# myDuinoMini_v1_0.net
KiCad netlist of a schematic drawn in EAGLE
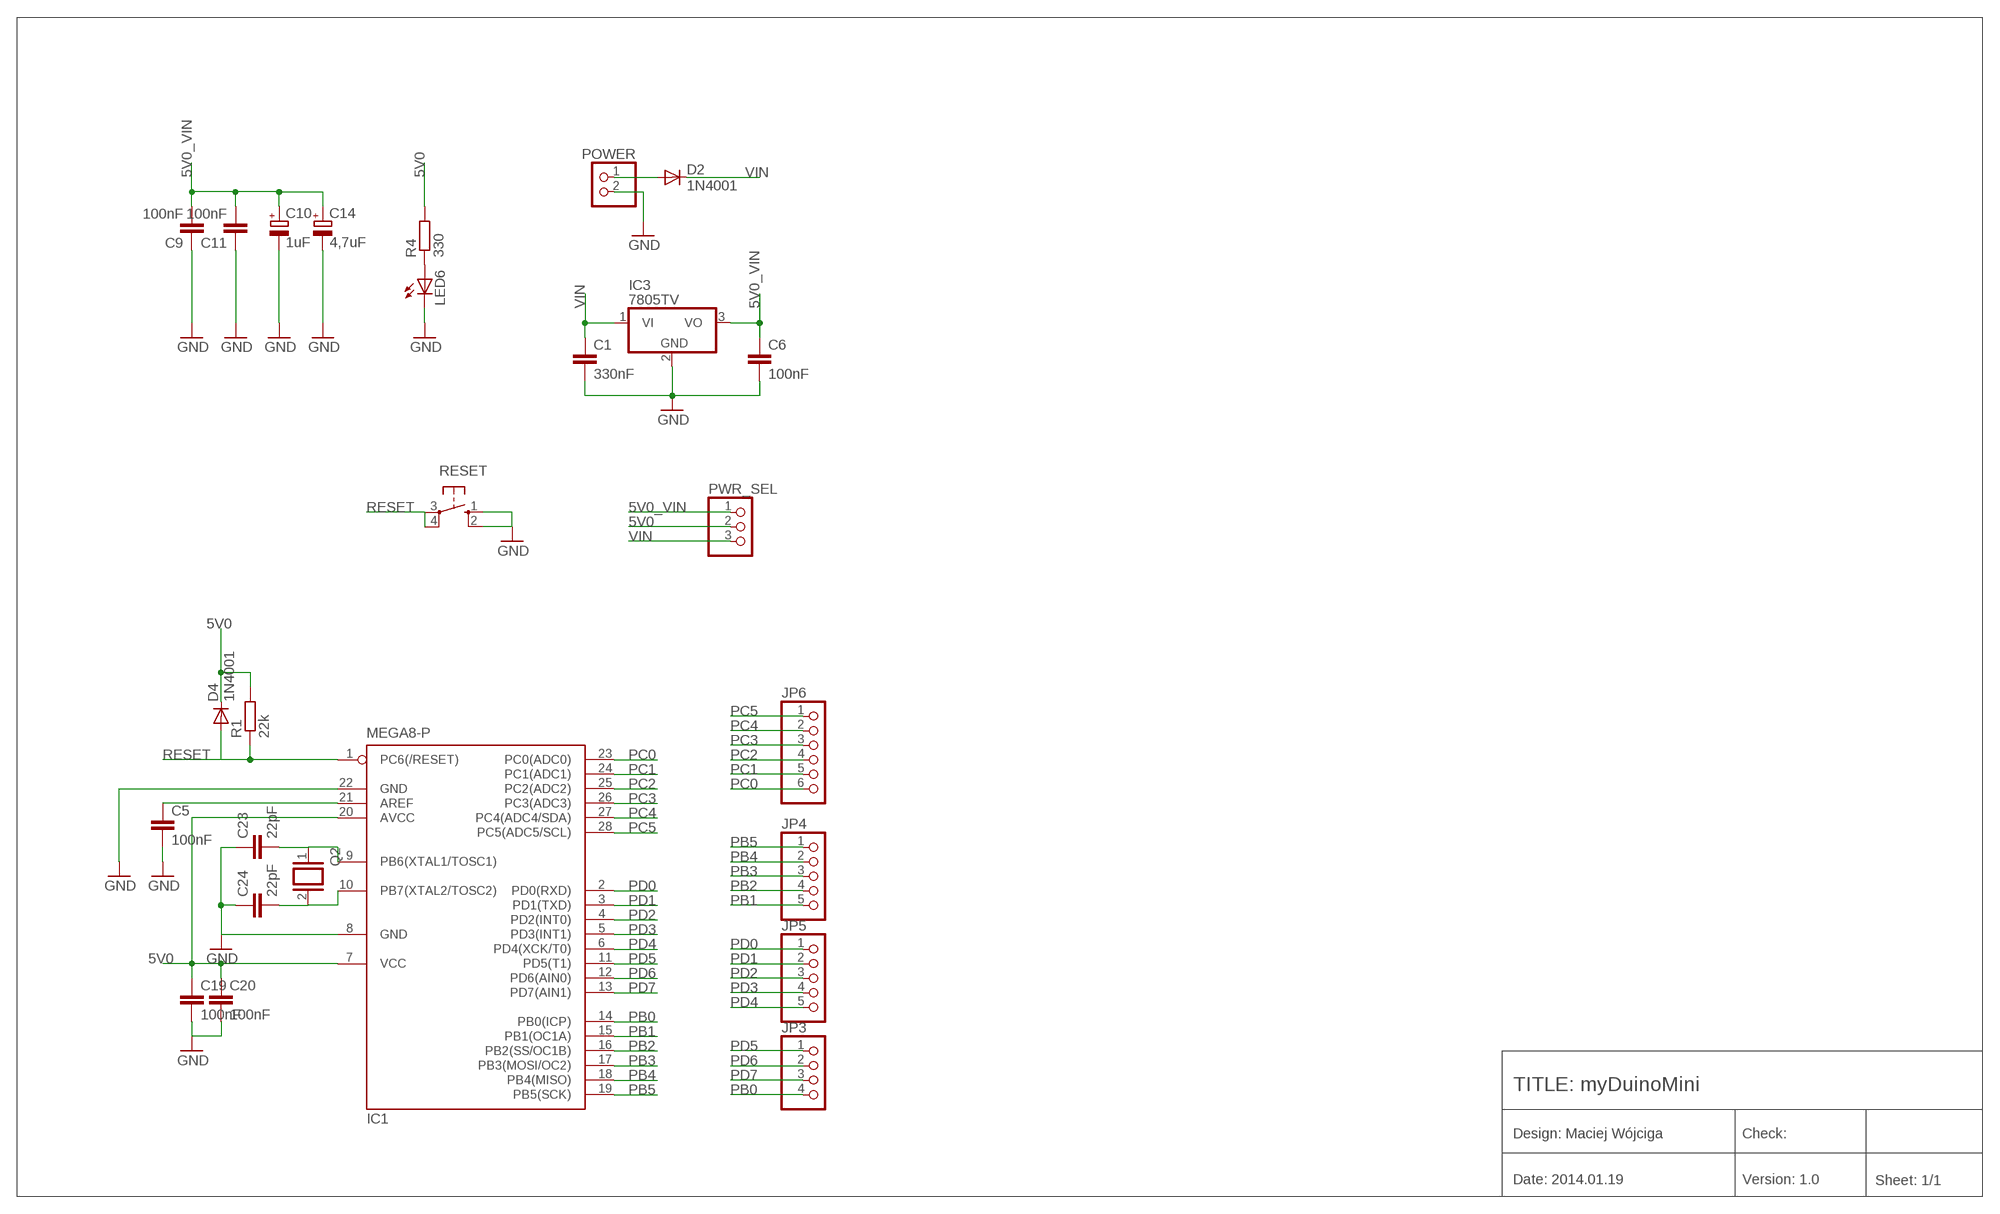
[diagram p0: schematic, sheet 1]

(export (version "E")
  (design (tool "Eeschema 10.0.6"))
  (components
    (comp (ref "C1")
      (value "330nF")
      (footprint "eagle-import:C025-025X050")
      (libsource (lib "eagle-import") (part "C-EU025-025X050"))
    )
    (comp (ref "C5")
      (value "100nF")
      (footprint "eagle-import:C025-025X050")
      (libsource (lib "eagle-import") (part "C-EU025-025X050"))
    )
    (comp (ref "C6")
      (value "100nF")
      (footprint "eagle-import:C025-025X050")
      (libsource (lib "eagle-import") (part "C-EU025-025X050"))
    )
    (comp (ref "C9")
      (value "100nF")
      (footprint "eagle-import:C025-025X050")
      (libsource (lib "eagle-import") (part "C-EU025-025X050"))
    )
    (comp (ref "C10")
      (value "1uF")
      (footprint "eagle-import:E2,5-5")
      (libsource (lib "eagle-import") (part "CPOL-EUE2.5-5"))
    )
    (comp (ref "C11")
      (value "100nF")
      (footprint "eagle-import:C025-025X050")
      (libsource (lib "eagle-import") (part "C-EU025-025X050"))
    )
    (comp (ref "C14")
      (value "4,7uF")
      (footprint "eagle-import:E2,5-5")
      (libsource (lib "eagle-import") (part "CPOL-EUE2.5-5"))
    )
    (comp (ref "C19")
      (value "100nF")
      (footprint "eagle-import:C025-025X050")
      (libsource (lib "eagle-import") (part "C-EU025-025X050"))
    )
    (comp (ref "C20")
      (value "100nF")
      (footprint "eagle-import:C025-025X050")
      (libsource (lib "eagle-import") (part "C-EU025-025X050"))
    )
    (comp (ref "C23")
      (value "22pF")
      (footprint "eagle-import:C025-025X050")
      (libsource (lib "eagle-import") (part "C-EU025-025X050"))
    )
    (comp (ref "C24")
      (value "22pF")
      (footprint "eagle-import:C025-025X050")
      (libsource (lib "eagle-import") (part "C-EU025-025X050"))
    )
    (comp (ref "D2")
      (value "1N4001")
      (footprint "eagle-import:DO41-10")
      (libsource (lib "eagle-import") (part "1N4004"))
    )
    (comp (ref "D4")
      (value "1N4001")
      (footprint "eagle-import:DO41-10")
      (libsource (lib "eagle-import") (part "1N4004"))
    )
    (comp (ref "IC1")
      (value "MEGA8-P")
      (footprint "eagle-import:DIL28-3")
      (libsource (lib "eagle-import") (part "MEGA8-P"))
    )
    (comp (ref "IC3")
      (value "7805TV")
      (footprint "eagle-import:TO220V")
      (libsource (lib "eagle-import") (part "78TV05"))
    )
    (comp (ref "JP3")
      (value "PINHD-1X4")
      (footprint "eagle-import:1X04")
      (libsource (lib "eagle-import") (part "PINHD-1X4"))
    )
    (comp (ref "JP4")
      (value "PINHD-1X5")
      (footprint "eagle-import:1X05")
      (libsource (lib "eagle-import") (part "PINHD-1X5"))
    )
    (comp (ref "JP5")
      (value "PINHD-1X5")
      (footprint "eagle-import:1X05")
      (libsource (lib "eagle-import") (part "PINHD-1X5"))
    )
    (comp (ref "JP6")
      (value "PINHD-1X6")
      (footprint "eagle-import:1X06")
      (libsource (lib "eagle-import") (part "PINHD-1X6"))
    )
    (comp (ref "LED6")
      (value "LED3MM")
      (footprint "eagle-import:LED3MM")
      (libsource (lib "eagle-import") (part "LED3MM"))
    )
    (comp (ref "POWER")
      (value "PINHD-1X2")
      (footprint "eagle-import:1X02")
      (libsource (lib "eagle-import") (part "PINHD-1X2"))
    )
    (comp (ref "PWR_SEL")
      (value "PINHD-1X3")
      (footprint "eagle-import:1X03")
      (libsource (lib "eagle-import") (part "PINHD-1X3"))
    )
    (comp (ref "Q2")
      (value "XTAL/S")
      (footprint "eagle-import:QS")
      (libsource (lib "eagle-import") (part "XTAL/S"))
    )
    (comp (ref "R1")
      (value "22k")
      (footprint "eagle-import:0207_10")
      (libsource (lib "eagle-import") (part "R-EU_0207/10"))
    )
    (comp (ref "R4")
      (value "330")
      (footprint "eagle-import:0207_10")
      (libsource (lib "eagle-import") (part "R-EU_0207/10"))
    )
    (comp (ref "RESET")
      (value "10-XX")
      (footprint "eagle-import:B3F-10XX")
      (fields (field (name "MPN") "B3F-1000"))
      (libsource (lib "eagle-import") (part "10-XX"))
    )
  )
  (nets
    (net (code "1") (name "/5V0") (class "Default")
      (node (ref "C19") (pin "1") (pinfunction "1_1") (pintype "passive"))
      (node (ref "C20") (pin "1") (pinfunction "1_1") (pintype "passive"))
      (node (ref "D4") (pin "C") (pinfunction "C_C") (pintype "passive"))
      (node (ref "IC1") (pin "20") (pinfunction "AVCC_20") (pintype "power_in"))
      (node (ref "IC1") (pin "7") (pinfunction "VCC_7") (pintype "power_in"))
      (node (ref "PWR_SEL") (pin "2") (pinfunction "2_2") (pintype "passive"))
      (node (ref "R1") (pin "2") (pinfunction "2_2") (pintype "passive"))
      (node (ref "R4") (pin "2") (pinfunction "2_2") (pintype "passive"))
    )
    (net (code "2") (name "/5V0_VIN") (class "Default")
      (node (ref "C10") (pin "+") (pinfunction "+_+") (pintype "passive"))
      (node (ref "C11") (pin "2") (pinfunction "2_2") (pintype "passive"))
      (node (ref "C14") (pin "+") (pinfunction "+_+") (pintype "passive"))
      (node (ref "C6") (pin "1") (pinfunction "1_1") (pintype "passive"))
      (node (ref "C9") (pin "2") (pinfunction "2_2") (pintype "passive"))
      (node (ref "IC3") (pin "3") (pinfunction "VO_3") (pintype "passive"))
      (node (ref "PWR_SEL") (pin "1") (pinfunction "1_1") (pintype "passive"))
    )
    (net (code "3") (name "/PB0") (class "Default")
      (node (ref "IC1") (pin "14") (pinfunction "PB0(ICP)_14") (pintype "bidirectional"))
      (node (ref "JP3") (pin "4") (pinfunction "4_4") (pintype "passive"))
    )
    (net (code "4") (name "/PB1") (class "Default")
      (node (ref "IC1") (pin "15") (pinfunction "PB1(OC1A)_15") (pintype "bidirectional"))
      (node (ref "JP4") (pin "5") (pinfunction "5_5") (pintype "passive"))
    )
    (net (code "5") (name "/PB2") (class "Default")
      (node (ref "IC1") (pin "16") (pinfunction "PB2(SS/OC1B)_16") (pintype "bidirectional"))
      (node (ref "JP4") (pin "4") (pinfunction "4_4") (pintype "passive"))
    )
    (net (code "6") (name "/PB3") (class "Default")
      (node (ref "IC1") (pin "17") (pinfunction "PB3(MOSI/OC2)_17") (pintype "bidirectional"))
      (node (ref "JP4") (pin "3") (pinfunction "3_3") (pintype "passive"))
    )
    (net (code "7") (name "/PB4") (class "Default")
      (node (ref "IC1") (pin "18") (pinfunction "PB4(MISO)_18") (pintype "bidirectional"))
      (node (ref "JP4") (pin "2") (pinfunction "2_2") (pintype "passive"))
    )
    (net (code "8") (name "/PB5") (class "Default")
      (node (ref "IC1") (pin "19") (pinfunction "PB5(SCK)_19") (pintype "bidirectional"))
      (node (ref "JP4") (pin "1") (pinfunction "1_1") (pintype "passive"))
    )
    (net (code "9") (name "/PC0") (class "Default")
      (node (ref "IC1") (pin "23") (pinfunction "PC0(ADC0)_23") (pintype "bidirectional"))
      (node (ref "JP6") (pin "6") (pinfunction "6_6") (pintype "passive"))
    )
    (net (code "10") (name "/PC1") (class "Default")
      (node (ref "IC1") (pin "24") (pinfunction "PC1(ADC1)_24") (pintype "bidirectional"))
      (node (ref "JP6") (pin "5") (pinfunction "5_5") (pintype "passive"))
    )
    (net (code "11") (name "/PC2") (class "Default")
      (node (ref "IC1") (pin "25") (pinfunction "PC2(ADC2)_25") (pintype "bidirectional"))
      (node (ref "JP6") (pin "4") (pinfunction "4_4") (pintype "passive"))
    )
    (net (code "12") (name "/PC3") (class "Default")
      (node (ref "IC1") (pin "26") (pinfunction "PC3(ADC3)_26") (pintype "bidirectional"))
      (node (ref "JP6") (pin "3") (pinfunction "3_3") (pintype "passive"))
    )
    (net (code "13") (name "/PC4") (class "Default")
      (node (ref "IC1") (pin "27") (pinfunction "PC4(ADC4/SDA)_27") (pintype "bidirectional"))
      (node (ref "JP6") (pin "2") (pinfunction "2_2") (pintype "passive"))
    )
    (net (code "14") (name "/PC5") (class "Default")
      (node (ref "IC1") (pin "28") (pinfunction "PC5(ADC5/SCL)_28") (pintype "bidirectional"))
      (node (ref "JP6") (pin "1") (pinfunction "1_1") (pintype "passive"))
    )
    (net (code "15") (name "/PD0") (class "Default")
      (node (ref "IC1") (pin "2") (pinfunction "PD0(RXD)_2") (pintype "bidirectional"))
      (node (ref "JP5") (pin "1") (pinfunction "1_1") (pintype "passive"))
    )
    (net (code "16") (name "/PD1") (class "Default")
      (node (ref "IC1") (pin "3") (pinfunction "PD1(TXD)_3") (pintype "bidirectional"))
      (node (ref "JP5") (pin "2") (pinfunction "2_2") (pintype "passive"))
    )
    (net (code "17") (name "/PD2") (class "Default")
      (node (ref "IC1") (pin "4") (pinfunction "PD2(INT0)_4") (pintype "bidirectional"))
      (node (ref "JP5") (pin "3") (pinfunction "3_3") (pintype "passive"))
    )
    (net (code "18") (name "/PD3") (class "Default")
      (node (ref "IC1") (pin "5") (pinfunction "PD3(INT1)_5") (pintype "bidirectional"))
      (node (ref "JP5") (pin "4") (pinfunction "4_4") (pintype "passive"))
    )
    (net (code "19") (name "/PD4") (class "Default")
      (node (ref "IC1") (pin "6") (pinfunction "PD4(XCK/T0)_6") (pintype "bidirectional"))
      (node (ref "JP5") (pin "5") (pinfunction "5_5") (pintype "passive"))
    )
    (net (code "20") (name "/PD5") (class "Default")
      (node (ref "IC1") (pin "11") (pinfunction "PD5(T1)_11") (pintype "bidirectional"))
      (node (ref "JP3") (pin "1") (pinfunction "1_1") (pintype "passive"))
    )
    (net (code "21") (name "/PD6") (class "Default")
      (node (ref "IC1") (pin "12") (pinfunction "PD6(AIN0)_12") (pintype "bidirectional"))
      (node (ref "JP3") (pin "2") (pinfunction "2_2") (pintype "passive"))
    )
    (net (code "22") (name "/PD7") (class "Default")
      (node (ref "IC1") (pin "13") (pinfunction "PD7(AIN1)_13") (pintype "bidirectional"))
      (node (ref "JP3") (pin "3") (pinfunction "3_3") (pintype "passive"))
    )
    (net (code "23") (name "/RESET") (class "Default")
      (node (ref "D4") (pin "A") (pinfunction "A_A") (pintype "passive"))
      (node (ref "IC1") (pin "1") (pinfunction "PC6(/RESET)_1") (pintype "bidirectional"))
      (node (ref "R1") (pin "1") (pinfunction "1_1") (pintype "passive"))
      (node (ref "RESET") (pin "3") (pinfunction "P_3") (pintype "passive"))
      (node (ref "RESET") (pin "4") (pinfunction "P1_4") (pintype "passive"))
    )
    (net (code "24") (name "/VIN") (class "Default")
      (node (ref "C1") (pin "1") (pinfunction "1_1") (pintype "passive"))
      (node (ref "D2") (pin "C") (pinfunction "C_C") (pintype "passive"))
      (node (ref "IC3") (pin "1") (pinfunction "VI_1") (pintype "input"))
      (node (ref "PWR_SEL") (pin "3") (pinfunction "3_3") (pintype "passive"))
    )
    (net (code "25") (name "GND") (class "Default")
      (node (ref "C1") (pin "2") (pinfunction "2_2") (pintype "passive"))
      (node (ref "C10") (pin "-") (pinfunction "-_-") (pintype "passive"))
      (node (ref "C11") (pin "1") (pinfunction "1_1") (pintype "passive"))
      (node (ref "C14") (pin "-") (pinfunction "-_-") (pintype "passive"))
      (node (ref "C19") (pin "2") (pinfunction "2_2") (pintype "passive"))
      (node (ref "C20") (pin "2") (pinfunction "2_2") (pintype "passive"))
      (node (ref "C23") (pin "1") (pinfunction "1_1") (pintype "passive"))
      (node (ref "C24") (pin "1") (pinfunction "1_1") (pintype "passive"))
      (node (ref "C5") (pin "2") (pinfunction "2_2") (pintype "passive"))
      (node (ref "C6") (pin "2") (pinfunction "2_2") (pintype "passive"))
      (node (ref "C9") (pin "1") (pinfunction "1_1") (pintype "passive"))
      (node (ref "IC1") (pin "22") (pinfunction "GND_22") (pintype "power_in"))
      (node (ref "IC1") (pin "8") (pinfunction "GND_8") (pintype "power_in"))
      (node (ref "IC3") (pin "2") (pinfunction "GND_2") (pintype "passive"))
      (node (ref "LED6") (pin "K") (pinfunction "C_K") (pintype "passive"))
      (node (ref "POWER") (pin "2") (pinfunction "2_2") (pintype "passive"))
      (node (ref "RESET") (pin "1") (pinfunction "S_1") (pintype "passive"))
      (node (ref "RESET") (pin "2") (pinfunction "S1_2") (pintype "passive"))
    )
    (net (code "26") (name "Net-(D2-PadA)") (class "Default")
      (node (ref "D2") (pin "A") (pinfunction "A_A") (pintype "passive"))
      (node (ref "POWER") (pin "1") (pinfunction "1_1") (pintype "passive"))
    )
    (net (code "27") (name "Net-(IC1-AREF)") (class "Default")
      (node (ref "C5") (pin "1") (pinfunction "1_1") (pintype "passive"))
      (node (ref "IC1") (pin "21") (pinfunction "AREF_21") (pintype "passive"))
    )
    (net (code "28") (name "Net-(IC1-PB6(XTAL1{slash}TOSC1))") (class "Default")
      (node (ref "C23") (pin "2") (pinfunction "2_2") (pintype "passive"))
      (node (ref "IC1") (pin "9") (pinfunction "PB6(XTAL1/TOSC1)_9") (pintype "bidirectional"))
      (node (ref "Q2") (pin "1") (pinfunction "1_1") (pintype "passive"))
    )
    (net (code "29") (name "Net-(IC1-PB7(XTAL2{slash}TOSC2))") (class "Default")
      (node (ref "C24") (pin "2") (pinfunction "2_2") (pintype "passive"))
      (node (ref "IC1") (pin "10") (pinfunction "PB7(XTAL2/TOSC2)_10") (pintype "bidirectional"))
      (node (ref "Q2") (pin "2") (pinfunction "2_2") (pintype "passive"))
    )
    (net (code "30") (name "Net-(LED6-PadA)") (class "Default")
      (node (ref "LED6") (pin "A") (pinfunction "A_A") (pintype "passive"))
      (node (ref "R4") (pin "1") (pinfunction "1_1") (pintype "passive"))
    )
  )
)
